# ESP32_CAN_V2-can.net
KiCad netlist of a schematic drawn in Altium Designer
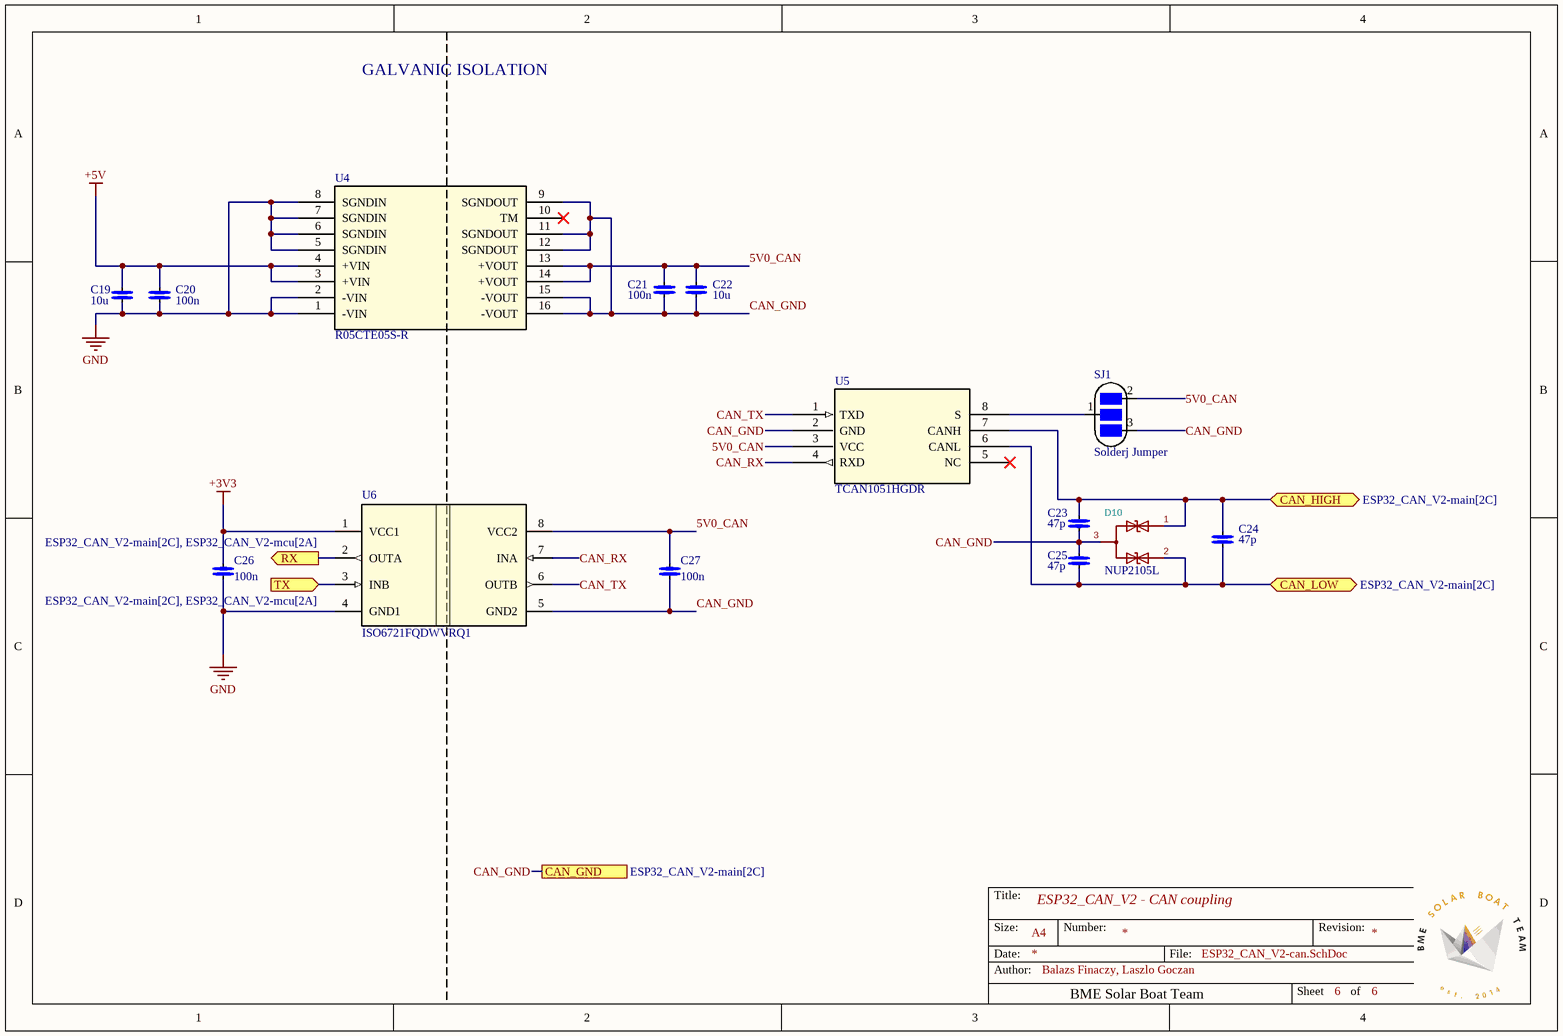
[diagram p0: ESP32_CAN_V2-can.SchDoc]

(export (version "E")
  (design (tool "Eeschema 10.0.6"))
  (components
    (comp (ref "C19") (value "10u") (footprint "C0805") (libsource (lib "ESP32_CAN_V2") (part "C")))
    (comp (ref "C20") (value "100n") (footprint "C0603") (libsource (lib "ESP32_CAN_V2") (part "C")))
    (comp (ref "C21") (value "100n") (footprint "C0603") (libsource (lib "ESP32_CAN_V2") (part "C")))
    (comp (ref "C22") (value "10u") (footprint "C0805") (libsource (lib "ESP32_CAN_V2") (part "C")))
    (comp (ref "C23") (value "47p") (footprint "C0603") (libsource (lib "ESP32_CAN_V2") (part "C")))
    (comp (ref "C24") (value "47p") (footprint "C0603") (libsource (lib "ESP32_CAN_V2") (part "C")))
    (comp (ref "C25") (value "47p") (footprint "C0603") (libsource (lib "ESP32_CAN_V2") (part "C")))
    (comp (ref "C26") (value "100n") (footprint "C0603") (libsource (lib "ESP32_CAN_V2") (part "C")))
    (comp (ref "C27") (value "100n") (footprint "C0603") (libsource (lib "ESP32_CAN_V2") (part "C")))
    (comp (ref "D10")
      (value "NUP2105L")
      (footprint "SOT-23")
      (libsource (lib "ESP32_CAN_V2") (part "TVS-Bidirectional-Diode_Dual"))
    )
    (comp (ref "SJ1")
      (value "Solderj Jumper")
      (footprint "SolderJumper 1x2")
      (libsource (lib "ESP32_CAN_V2") (part "Solder Jumper 1x2"))
    )
    (comp (ref "U4")
      (value "R05CTE05S-R")
      (footprint "SMD_16_10.35X7.5X2.5_RCP")
      (description "DC/DC converter")
      (fields (field (name "COPYRIGHT") "Copyright (C) 2026 Ultra Librarian. All rights reserved."))
      (libsource (lib "ESP32_CAN_V2") (part "R05CTE05S-R"))
    )
    (comp (ref "U5")
      (value "TCAN1051HGDR")
      (footprint "D8_TEX")
      (description "Fault Protected CAN Transceiver With Flexible Data-Rate 8-SOIC -55 to 125")
      (fields (field (name "COPYRIGHT") "Copyright (C) 2026 Ultra Librarian. All rights reserved."))
      (libsource (lib "ESP32_CAN_V2") (part "TCAN1051HGDR"))
    )
    (comp (ref "U6")
      (value "ISO6721FQDWVRQ1")
      (footprint "DWV0008A-IPC_A")
      (description "Automotive, general-purpose, dual-channel, 1/1 digital isolator 8-SOIC -40 to 125")
      (fields (field (name "COPYRIGHT") "Copyright (C) 2026 Ultra Librarian. All rights reserved."))
      (libsource (lib "ESP32_CAN_V2") (part "ISO6721FQDWVRQ1"))
    )
  )
  (nets
    (net (code "1") (name "+3V3") (class "Default")
      (node (ref "C26") (pin "2") (pinfunction "2_2") (pintype "passive"))
      (node (ref "U6") (pin "1") (pinfunction "VCC1_1") (pintype "power_in"))
    )
    (net (code "2") (name "+5V") (class "Default")
      (node (ref "C19") (pin "2") (pinfunction "2_2") (pintype "passive"))
      (node (ref "C20") (pin "2") (pinfunction "2_2") (pintype "passive"))
      (node (ref "U4") (pin "3") (pinfunction "+VIN_3") (pintype "power_in"))
      (node (ref "U4") (pin "4") (pinfunction "+VIN_4") (pintype "power_in"))
    )
    (net (code "3") (name "/5V0_CAN") (class "Default")
      (node (ref "C21") (pin "2") (pinfunction "2_2") (pintype "passive"))
      (node (ref "C22") (pin "2") (pinfunction "2_2") (pintype "passive"))
      (node (ref "C27") (pin "2") (pinfunction "2_2") (pintype "passive"))
      (node (ref "SJ1") (pin "2") (pinfunction "2_2") (pintype "passive"))
      (node (ref "U4") (pin "13") (pinfunction "+VOUT_13") (pintype "power_in"))
      (node (ref "U4") (pin "14") (pinfunction "+VOUT_14") (pintype "power_in"))
      (node (ref "U5") (pin "3") (pinfunction "VCC_3") (pintype "power_in"))
      (node (ref "U6") (pin "8") (pinfunction "VCC2_8") (pintype "power_in"))
    )
    (net (code "4") (name "/CAN_GND") (class "Default")
      (node (ref "C21") (pin "1") (pinfunction "1_1") (pintype "passive"))
      (node (ref "C22") (pin "1") (pinfunction "1_1") (pintype "passive"))
      (node (ref "C23") (pin "1") (pinfunction "1_1") (pintype "passive"))
      (node (ref "C25") (pin "2") (pinfunction "2_2") (pintype "passive"))
      (node (ref "C27") (pin "1") (pinfunction "1_1") (pintype "passive"))
      (node (ref "D10") (pin "3") (pinfunction "3_3") (pintype "passive"))
      (node (ref "SJ1") (pin "3") (pinfunction "3_3") (pintype "passive"))
      (node (ref "U4") (pin "11") (pinfunction "SGNDOUT_11") (pintype "power_in"))
      (node (ref "U4") (pin "12") (pinfunction "SGNDOUT_12") (pintype "power_in"))
      (node (ref "U4") (pin "15") (pinfunction "-VOUT_15") (pintype "power_in"))
      (node (ref "U4") (pin "16") (pinfunction "-VOUT_16") (pintype "power_in"))
      (node (ref "U4") (pin "9") (pinfunction "SGNDOUT_9") (pintype "power_in"))
      (node (ref "U5") (pin "2") (pinfunction "GND_2") (pintype "power_in"))
      (node (ref "U6") (pin "5") (pinfunction "GND2_5") (pintype "power_in"))
    )
    (net (code "5") (name "/CAN_HIGH") (class "Default")
      (node (ref "C23") (pin "2") (pinfunction "2_2") (pintype "passive"))
      (node (ref "C24") (pin "2") (pinfunction "2_2") (pintype "passive"))
      (node (ref "D10") (pin "1") (pinfunction "1_1") (pintype "passive"))
      (node (ref "U5") (pin "7") (pinfunction "CANH_7") (pintype "passive"))
    )
    (net (code "6") (name "/CAN_LOW") (class "Default")
      (node (ref "C24") (pin "1") (pinfunction "1_1") (pintype "passive"))
      (node (ref "C25") (pin "1") (pinfunction "1_1") (pintype "passive"))
      (node (ref "D10") (pin "2") (pinfunction "2_2") (pintype "passive"))
      (node (ref "U5") (pin "6") (pinfunction "CANL_6") (pintype "passive"))
    )
    (net (code "7") (name "/CAN_RX") (class "Default")
      (node (ref "U5") (pin "4") (pinfunction "RXD_4") (pintype "output"))
      (node (ref "U6") (pin "7") (pinfunction "INA_7") (pintype "input"))
    )
    (net (code "8") (name "/CAN_TX") (class "Default")
      (node (ref "U5") (pin "1") (pinfunction "TXD_1") (pintype "input"))
      (node (ref "U6") (pin "6") (pinfunction "OUTB_6") (pintype "output"))
    )
    (net (code "9") (name "/RX") (class "Default")
      (node (ref "U6") (pin "2") (pinfunction "OUTA_2") (pintype "output"))
    )
    (net (code "10") (name "/TX") (class "Default")
      (node (ref "U6") (pin "3") (pinfunction "INB_3") (pintype "input"))
    )
    (net (code "11") (name "GND") (class "Default")
      (node (ref "C19") (pin "1") (pinfunction "1_1") (pintype "passive"))
      (node (ref "C20") (pin "1") (pinfunction "1_1") (pintype "passive"))
      (node (ref "C26") (pin "1") (pinfunction "1_1") (pintype "passive"))
      (node (ref "U4") (pin "1") (pinfunction "-VIN_1") (pintype "power_in"))
      (node (ref "U4") (pin "2") (pinfunction "-VIN_2") (pintype "power_in"))
      (node (ref "U4") (pin "5") (pinfunction "SGNDIN_5") (pintype "power_in"))
      (node (ref "U4") (pin "6") (pinfunction "SGNDIN_6") (pintype "power_in"))
      (node (ref "U4") (pin "7") (pinfunction "SGNDIN_7") (pintype "power_in"))
      (node (ref "U4") (pin "8") (pinfunction "SGNDIN_8") (pintype "power_in"))
      (node (ref "U6") (pin "4") (pinfunction "GND1_4") (pintype "power_in"))
    )
    (net (code "12") (name "Net-(U5-S)") (class "Default")
      (node (ref "SJ1") (pin "1") (pinfunction "1_1") (pintype "passive"))
      (node (ref "U5") (pin "8") (pinfunction "S_8") (pintype "passive"))
    )
    (net (code "13") (name "unconnected-(U4-TM-Pad10)") (class "Default")
      (node (ref "U4") (pin "10") (pinfunction "TM_10") (pintype "passive+no_connect"))
    )
    (net (code "14") (name "unconnected-(U5-NC-Pad5)") (class "Default")
      (node (ref "U5") (pin "5") (pinfunction "NC_5") (pintype "passive+no_connect"))
    )
  )
)
